# OpenBlinds.net
KiCad netlist of a schematic drawn in EAGLE
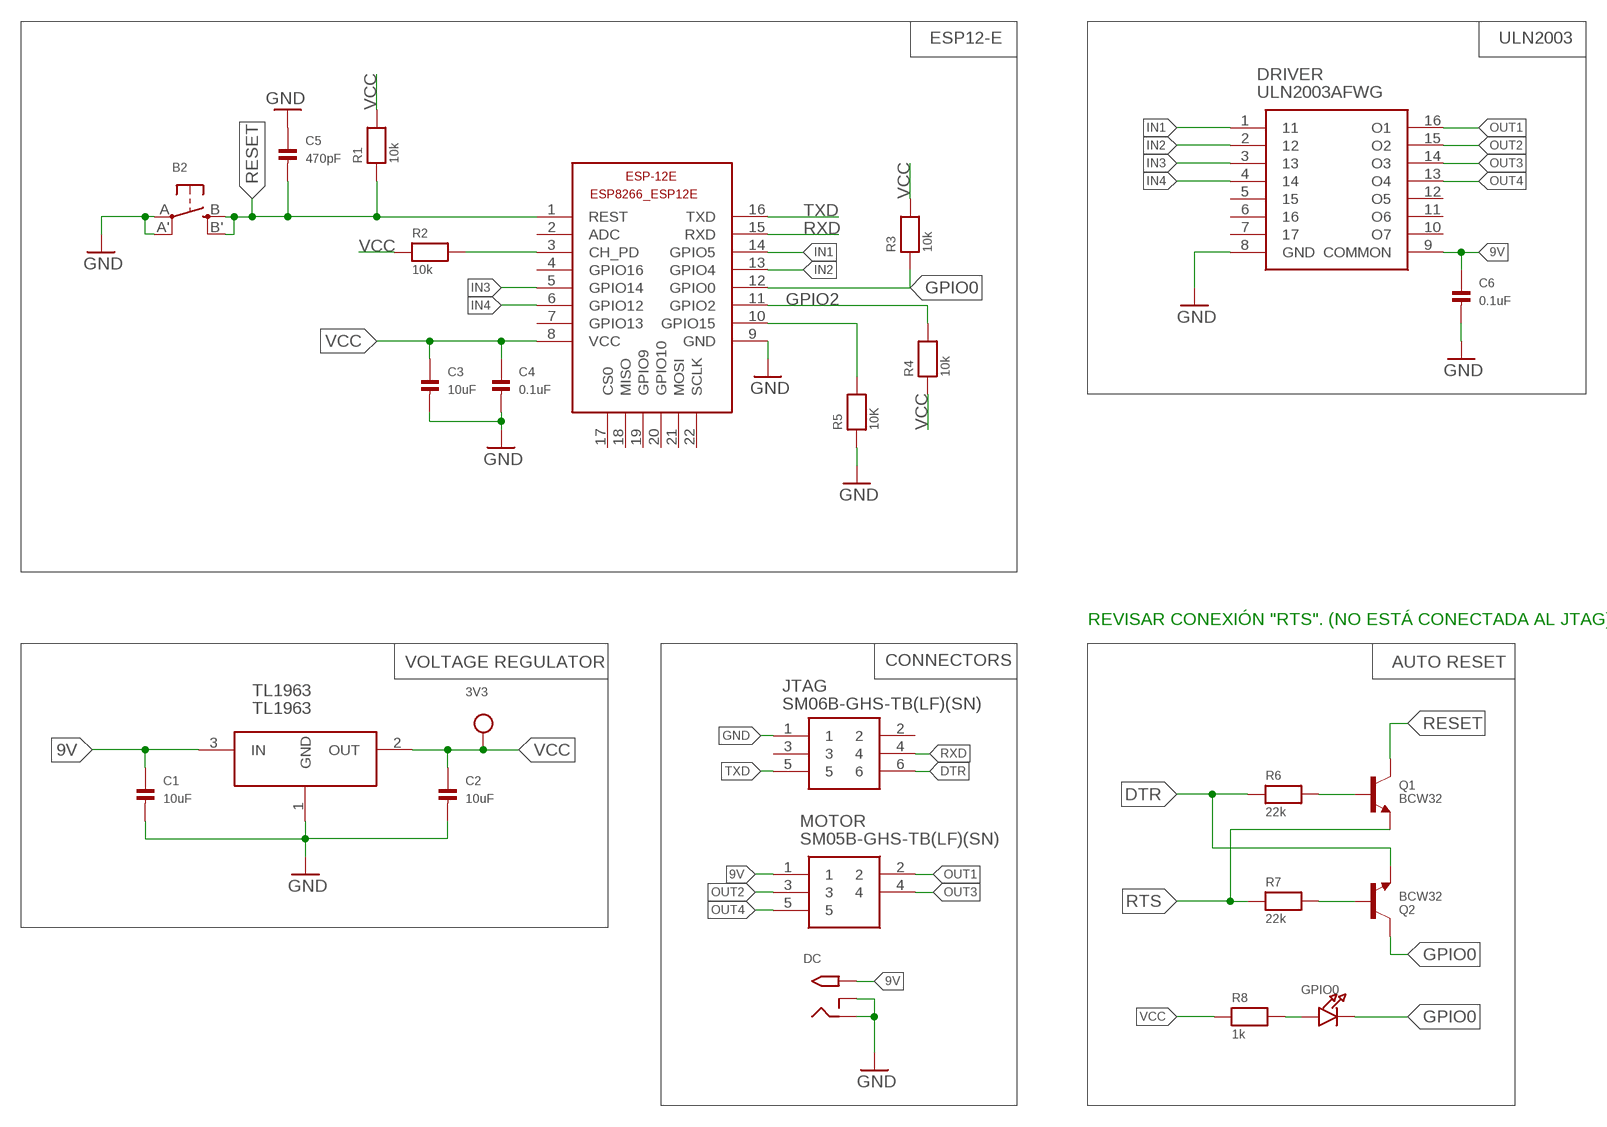
[diagram p0: schematic, sheet 1]

(export (version "E")
  (design (tool "Eeschema 10.0.6"))
  (components
    (comp (ref "3V3")
      (value "TESTPOINTROUND1MM")
      (footprint "eagle-import:TESTPOINT_ROUND_1MM")
      (libsource (lib "eagle-import") (part "TESTPOINTROUND1MM"))
    )
    (comp (ref "B2")
      (value "SWITCH_TACT_SMT4.6X2.8")
      (footprint "eagle-import:BTN_KMR2_4.6X2.8")
      (libsource (lib "eagle-import") (part "SWITCH_TACT_SMT4.6X2.8"))
    )
    (comp (ref "C1")
      (value "10uF")
      (footprint "eagle-import:_0603")
      (libsource (lib "eagle-import") (part "CAP_CERAMIC_0603"))
    )
    (comp (ref "C2")
      (value "10uF")
      (footprint "eagle-import:_0603")
      (libsource (lib "eagle-import") (part "CAP_CERAMIC_0603"))
    )
    (comp (ref "C3")
      (value "10uF")
      (footprint "eagle-import:_0603")
      (libsource (lib "eagle-import") (part "CAP_CERAMIC_0603"))
    )
    (comp (ref "C4")
      (value "0.1uF")
      (footprint "eagle-import:_0603")
      (libsource (lib "eagle-import") (part "CAP_CERAMIC_0603"))
    )
    (comp (ref "C5")
      (value "470pF")
      (footprint "eagle-import:_0603")
      (libsource (lib "eagle-import") (part "CAP_CERAMIC_0603"))
    )
    (comp (ref "C6")
      (value "0.1uF")
      (footprint "eagle-import:_0603")
      (libsource (lib "eagle-import") (part "CAP_CERAMIC_0603"))
    )
    (comp (ref "DC")
      (value "2.1MMJACKTHM")
      (footprint "eagle-import:PJ-102A")
      (libsource (lib "eagle-import") (part "2.1MMJACKTHM"))
    )
    (comp (ref "DRIVER")
      (value "ULN2003AFWG")
      (footprint "eagle-import:SOIC127P562X173-16N")
      (libsource (lib "eagle-import") (part "ULN2003AFWG"))
    )
    (comp (ref "ESP-12E")
      (value "ESP-12E")
      (footprint "eagle-import:ESP8266-ESP12E")
      (libsource (lib "eagle-import") (part "ESP8266-12EESP8266-ESP12E"))
    )
    (comp (ref "GPIO0")
      (value "LED0603")
      (footprint "eagle-import:CHIPLED_0603")
      (libsource (lib "eagle-import") (part "LED0603"))
    )
    (comp (ref "JTAG")
      (value "SM06B-GHS-TB(LF)(SN)")
      (footprint "eagle-import:SM06B-GHS-TB")
      (fields (field (name "RS_PART_NUMBER") "7521800P"))
      (libsource (lib "eagle-import") (part "SM06B-GHS-TB(LF)(SN)"))
    )
    (comp (ref "MOTOR")
      (value "SM05B-GHS-TB(LF)(SN)")
      (footprint "eagle-import:SM05B-GHS-TB")
      (fields (field (name "RS_PART_NUMBER") "7521807P"))
      (libsource (lib "eagle-import") (part "SM05B-GHS-TB(LF)(SN)"))
    )
    (comp (ref "Q1")
      (value "BCW32")
      (footprint "eagle-import:SOT23-R")
      (libsource (lib "eagle-import") (part "TRANSISTOR_NPN"))
    )
    (comp (ref "Q2")
      (value "BCW32")
      (footprint "eagle-import:SOT23-R")
      (libsource (lib "eagle-import") (part "TRANSISTOR_NPN"))
    )
    (comp (ref "R1")
      (value "10k")
      (footprint "eagle-import:_0603")
      (libsource (lib "eagle-import") (part "RESISTOR_0603"))
    )
    (comp (ref "R2")
      (value "10k")
      (footprint "eagle-import:_0603")
      (libsource (lib "eagle-import") (part "RESISTOR_0603"))
    )
    (comp (ref "R3")
      (value "10k")
      (footprint "eagle-import:_0603")
      (libsource (lib "eagle-import") (part "RESISTOR_0603"))
    )
    (comp (ref "R4")
      (value "10k")
      (footprint "eagle-import:_0603")
      (libsource (lib "eagle-import") (part "RESISTOR_0603"))
    )
    (comp (ref "R5")
      (value "10K")
      (footprint "eagle-import:_0603")
      (libsource (lib "eagle-import") (part "RESISTOR_0603"))
    )
    (comp (ref "R6")
      (value "22k")
      (footprint "eagle-import:_0603")
      (libsource (lib "eagle-import") (part "RESISTOR_0603"))
    )
    (comp (ref "R7")
      (value "22k")
      (footprint "eagle-import:_0603")
      (libsource (lib "eagle-import") (part "RESISTOR_0603"))
    )
    (comp (ref "R8")
      (value "1k")
      (footprint "eagle-import:_0603")
      (libsource (lib "eagle-import") (part "RESISTOR_0603"))
    )
    (comp (ref "TL1963")
      (value "TL1963")
      (footprint "eagle-import:SOT223")
      (libsource (lib "eagle-import") (part "NCP1117"))
    )
  )
  (nets
    (net (code "1") (name "/GPIO2") (class "Default")
      (node (ref "ESP-12E") (pin "11") (pinfunction "GPIO2_11") (pintype "bidirectional"))
      (node (ref "R4") (pin "2") (pinfunction "2_2") (pintype "passive"))
    )
    (net (code "2") (name "9V") (class "Default")
      (node (ref "C1") (pin "1") (pinfunction "P$1_1") (pintype "passive"))
      (node (ref "C6") (pin "1") (pinfunction "P$1_1") (pintype "passive"))
      (node (ref "DC") (pin "TIP") (pinfunction "TIP_TIP") (pintype "bidirectional"))
      (node (ref "DRIVER") (pin "9") (pinfunction "COMMON_9") (pintype "bidirectional"))
      (node (ref "MOTOR") (pin "1") (pinfunction "1_1") (pintype "bidirectional"))
      (node (ref "TL1963") (pin "3") (pinfunction "IN_3") (pintype "bidirectional"))
    )
    (net (code "3") (name "DTR") (class "Default")
      (node (ref "JTAG") (pin "6") (pinfunction "6_6") (pintype "bidirectional"))
      (node (ref "Q2") (pin "2") (pinfunction "E_2") (pintype "passive"))
      (node (ref "R6") (pin "1") (pinfunction "1_1") (pintype "passive"))
    )
    (net (code "4") (name "GND") (class "Default")
      (node (ref "B2") (pin "A") (pinfunction "P_A") (pintype "passive"))
      (node (ref "B2") (pin "A'") (pinfunction "P1_A'") (pintype "passive"))
      (node (ref "C1") (pin "2") (pinfunction "P$2_2") (pintype "passive"))
      (node (ref "C2") (pin "2") (pinfunction "P$2_2") (pintype "passive"))
      (node (ref "C3") (pin "2") (pinfunction "P$2_2") (pintype "passive"))
      (node (ref "C4") (pin "2") (pinfunction "P$2_2") (pintype "passive"))
      (node (ref "C5") (pin "1") (pinfunction "P$1_1") (pintype "passive"))
      (node (ref "C6") (pin "2") (pinfunction "P$2_2") (pintype "passive"))
      (node (ref "DC") (pin "RING") (pinfunction "RING_RING") (pintype "bidirectional"))
      (node (ref "DC") (pin "RING_SW") (pinfunction "RING_SW_RING_SW") (pintype "bidirectional"))
      (node (ref "DRIVER") (pin "8") (pinfunction "GND_8") (pintype "bidirectional"))
      (node (ref "ESP-12E") (pin "9") (pinfunction "GND_9") (pintype "bidirectional"))
      (node (ref "JTAG") (pin "1") (pinfunction "1_1") (pintype "bidirectional"))
      (node (ref "R5") (pin "1") (pinfunction "1_1") (pintype "passive"))
      (node (ref "TL1963") (pin "1") (pinfunction "GND_1") (pintype "bidirectional"))
    )
    (net (code "5") (name "GPIO0") (class "Default")
      (node (ref "ESP-12E") (pin "12") (pinfunction "GPIO0_12") (pintype "bidirectional"))
      (node (ref "GPIO0") (pin "C") (pinfunction "C_C") (pintype "passive"))
      (node (ref "Q2") (pin "3") (pinfunction "C_3") (pintype "passive"))
      (node (ref "R3") (pin "1") (pinfunction "1_1") (pintype "passive"))
    )
    (net (code "6") (name "IN1") (class "Default")
      (node (ref "DRIVER") (pin "1") (pinfunction "11_1") (pintype "bidirectional"))
      (node (ref "ESP-12E") (pin "14") (pinfunction "GPIO5_14") (pintype "bidirectional"))
    )
    (net (code "7") (name "IN2") (class "Default")
      (node (ref "DRIVER") (pin "2") (pinfunction "12_2") (pintype "bidirectional"))
      (node (ref "ESP-12E") (pin "13") (pinfunction "GPIO4_13") (pintype "bidirectional"))
    )
    (net (code "8") (name "IN3") (class "Default")
      (node (ref "DRIVER") (pin "3") (pinfunction "13_3") (pintype "bidirectional"))
      (node (ref "ESP-12E") (pin "5") (pinfunction "GPIO14_5") (pintype "bidirectional"))
    )
    (net (code "9") (name "IN4") (class "Default")
      (node (ref "DRIVER") (pin "4") (pinfunction "14_4") (pintype "bidirectional"))
      (node (ref "ESP-12E") (pin "6") (pinfunction "GPIO12_6") (pintype "bidirectional"))
    )
    (net (code "10") (name "Net-(ESP-12E-CH_PD)") (class "Default")
      (node (ref "ESP-12E") (pin "3") (pinfunction "CH_PD_3") (pintype "bidirectional"))
      (node (ref "R2") (pin "2") (pinfunction "2_2") (pintype "passive"))
    )
    (net (code "11") (name "Net-(ESP-12E-GPIO15)") (class "Default")
      (node (ref "ESP-12E") (pin "10") (pinfunction "GPIO15_10") (pintype "bidirectional"))
      (node (ref "R5") (pin "2") (pinfunction "2_2") (pintype "passive"))
    )
    (net (code "12") (name "Net-(GPIO0-PadA)") (class "Default")
      (node (ref "GPIO0") (pin "A") (pinfunction "A_A") (pintype "passive"))
      (node (ref "R8") (pin "2") (pinfunction "2_2") (pintype "passive"))
    )
    (net (code "13") (name "Net-(Q1-B)") (class "Default")
      (node (ref "Q1") (pin "1") (pinfunction "B_1") (pintype "passive"))
      (node (ref "R6") (pin "2") (pinfunction "2_2") (pintype "passive"))
    )
    (net (code "14") (name "Net-(Q2-B)") (class "Default")
      (node (ref "Q2") (pin "1") (pinfunction "B_1") (pintype "passive"))
      (node (ref "R7") (pin "2") (pinfunction "2_2") (pintype "passive"))
    )
    (net (code "15") (name "OUT1") (class "Default")
      (node (ref "DRIVER") (pin "16") (pinfunction "O1_16") (pintype "bidirectional"))
      (node (ref "MOTOR") (pin "2") (pinfunction "2_2") (pintype "bidirectional"))
    )
    (net (code "16") (name "OUT2") (class "Default")
      (node (ref "DRIVER") (pin "15") (pinfunction "O2_15") (pintype "bidirectional"))
      (node (ref "MOTOR") (pin "3") (pinfunction "3_3") (pintype "bidirectional"))
    )
    (net (code "17") (name "OUT3") (class "Default")
      (node (ref "DRIVER") (pin "14") (pinfunction "O3_14") (pintype "bidirectional"))
      (node (ref "MOTOR") (pin "4") (pinfunction "4_4") (pintype "bidirectional"))
    )
    (net (code "18") (name "OUT4") (class "Default")
      (node (ref "DRIVER") (pin "13") (pinfunction "O4_13") (pintype "bidirectional"))
      (node (ref "MOTOR") (pin "5") (pinfunction "5_5") (pintype "bidirectional"))
    )
    (net (code "19") (name "RESET") (class "Default")
      (node (ref "B2") (pin "B") (pinfunction "S_B") (pintype "passive"))
      (node (ref "B2") (pin "B'") (pinfunction "S1_B'") (pintype "passive"))
      (node (ref "C5") (pin "2") (pinfunction "P$2_2") (pintype "passive"))
      (node (ref "ESP-12E") (pin "1") (pinfunction "REST_1") (pintype "bidirectional"))
      (node (ref "Q1") (pin "3") (pinfunction "C_3") (pintype "passive"))
      (node (ref "R1") (pin "1") (pinfunction "1_1") (pintype "passive"))
    )
    (net (code "20") (name "RTS") (class "Default")
      (node (ref "Q1") (pin "2") (pinfunction "E_2") (pintype "passive"))
      (node (ref "R7") (pin "1") (pinfunction "1_1") (pintype "passive"))
    )
    (net (code "21") (name "RXD") (class "Default")
      (node (ref "ESP-12E") (pin "15") (pinfunction "RXD_15") (pintype "bidirectional"))
      (node (ref "JTAG") (pin "4") (pinfunction "4_4") (pintype "bidirectional"))
    )
    (net (code "22") (name "TXD") (class "Default")
      (node (ref "ESP-12E") (pin "16") (pinfunction "TXD_16") (pintype "bidirectional"))
      (node (ref "JTAG") (pin "5") (pinfunction "5_5") (pintype "bidirectional"))
    )
    (net (code "23") (name "VCC") (class "Default")
      (node (ref "3V3") (pin "P$1") (pinfunction "P$1_P$1") (pintype "bidirectional"))
      (node (ref "C2") (pin "1") (pinfunction "P$1_1") (pintype "passive"))
      (node (ref "C3") (pin "1") (pinfunction "P$1_1") (pintype "passive"))
      (node (ref "C4") (pin "1") (pinfunction "P$1_1") (pintype "passive"))
      (node (ref "ESP-12E") (pin "8") (pinfunction "VCC_8") (pintype "bidirectional"))
      (node (ref "R1") (pin "2") (pinfunction "2_2") (pintype "passive"))
      (node (ref "R2") (pin "1") (pinfunction "1_1") (pintype "passive"))
      (node (ref "R3") (pin "2") (pinfunction "2_2") (pintype "passive"))
      (node (ref "R4") (pin "1") (pinfunction "1_1") (pintype "passive"))
      (node (ref "R8") (pin "1") (pinfunction "1_1") (pintype "passive"))
      (node (ref "TL1963") (pin "2") (pinfunction "OUT_2") (pintype "bidirectional"))
    )
    (net (code "24") (name "unconnected-(DRIVER-15-Pad5)") (class "Default")
      (node (ref "DRIVER") (pin "5") (pinfunction "15_5") (pintype "bidirectional"))
    )
    (net (code "25") (name "unconnected-(DRIVER-16-Pad6)") (class "Default")
      (node (ref "DRIVER") (pin "6") (pinfunction "16_6") (pintype "bidirectional"))
    )
    (net (code "26") (name "unconnected-(DRIVER-17-Pad7)") (class "Default")
      (node (ref "DRIVER") (pin "7") (pinfunction "17_7") (pintype "bidirectional"))
    )
    (net (code "27") (name "unconnected-(DRIVER-O5-Pad12)") (class "Default")
      (node (ref "DRIVER") (pin "12") (pinfunction "O5_12") (pintype "bidirectional"))
    )
    (net (code "28") (name "unconnected-(DRIVER-O6-Pad11)") (class "Default")
      (node (ref "DRIVER") (pin "11") (pinfunction "O6_11") (pintype "bidirectional"))
    )
    (net (code "29") (name "unconnected-(DRIVER-O7-Pad10)") (class "Default")
      (node (ref "DRIVER") (pin "10") (pinfunction "O7_10") (pintype "bidirectional"))
    )
    (net (code "30") (name "unconnected-(ESP-12E-ADC-Pad2)") (class "Default")
      (node (ref "ESP-12E") (pin "2") (pinfunction "ADC_2") (pintype "bidirectional"))
    )
    (net (code "31") (name "unconnected-(ESP-12E-CS0-Pad17)") (class "Default")
      (node (ref "ESP-12E") (pin "17") (pinfunction "CS0_17") (pintype "bidirectional"))
    )
    (net (code "32") (name "unconnected-(ESP-12E-GPIO9-Pad19)") (class "Default")
      (node (ref "ESP-12E") (pin "19") (pinfunction "GPIO9_19") (pintype "bidirectional"))
    )
    (net (code "33") (name "unconnected-(ESP-12E-GPIO10-Pad20)") (class "Default")
      (node (ref "ESP-12E") (pin "20") (pinfunction "GPIO10_20") (pintype "bidirectional"))
    )
    (net (code "34") (name "unconnected-(ESP-12E-GPIO13-Pad7)") (class "Default")
      (node (ref "ESP-12E") (pin "7") (pinfunction "GPIO13_7") (pintype "bidirectional"))
    )
    (net (code "35") (name "unconnected-(ESP-12E-GPIO16-Pad4)") (class "Default")
      (node (ref "ESP-12E") (pin "4") (pinfunction "GPIO16_4") (pintype "bidirectional"))
    )
    (net (code "36") (name "unconnected-(ESP-12E-MISO-Pad18)") (class "Default")
      (node (ref "ESP-12E") (pin "18") (pinfunction "MISO_18") (pintype "bidirectional"))
    )
    (net (code "37") (name "unconnected-(ESP-12E-MOSI-Pad21)") (class "Default")
      (node (ref "ESP-12E") (pin "21") (pinfunction "MOSI_21") (pintype "bidirectional"))
    )
    (net (code "38") (name "unconnected-(ESP-12E-SCLK-Pad22)") (class "Default")
      (node (ref "ESP-12E") (pin "22") (pinfunction "SCLK_22") (pintype "bidirectional"))
    )
    (net (code "39") (name "unconnected-(JTAG-Pad2)") (class "Default")
      (node (ref "JTAG") (pin "2") (pinfunction "2_2") (pintype "bidirectional"))
    )
    (net (code "40") (name "unconnected-(JTAG-Pad3)") (class "Default")
      (node (ref "JTAG") (pin "3") (pinfunction "3_3") (pintype "bidirectional"))
    )
  )
)
